# MainBoard_XMega.net
KiCad netlist of a schematic drawn in Altium Designer
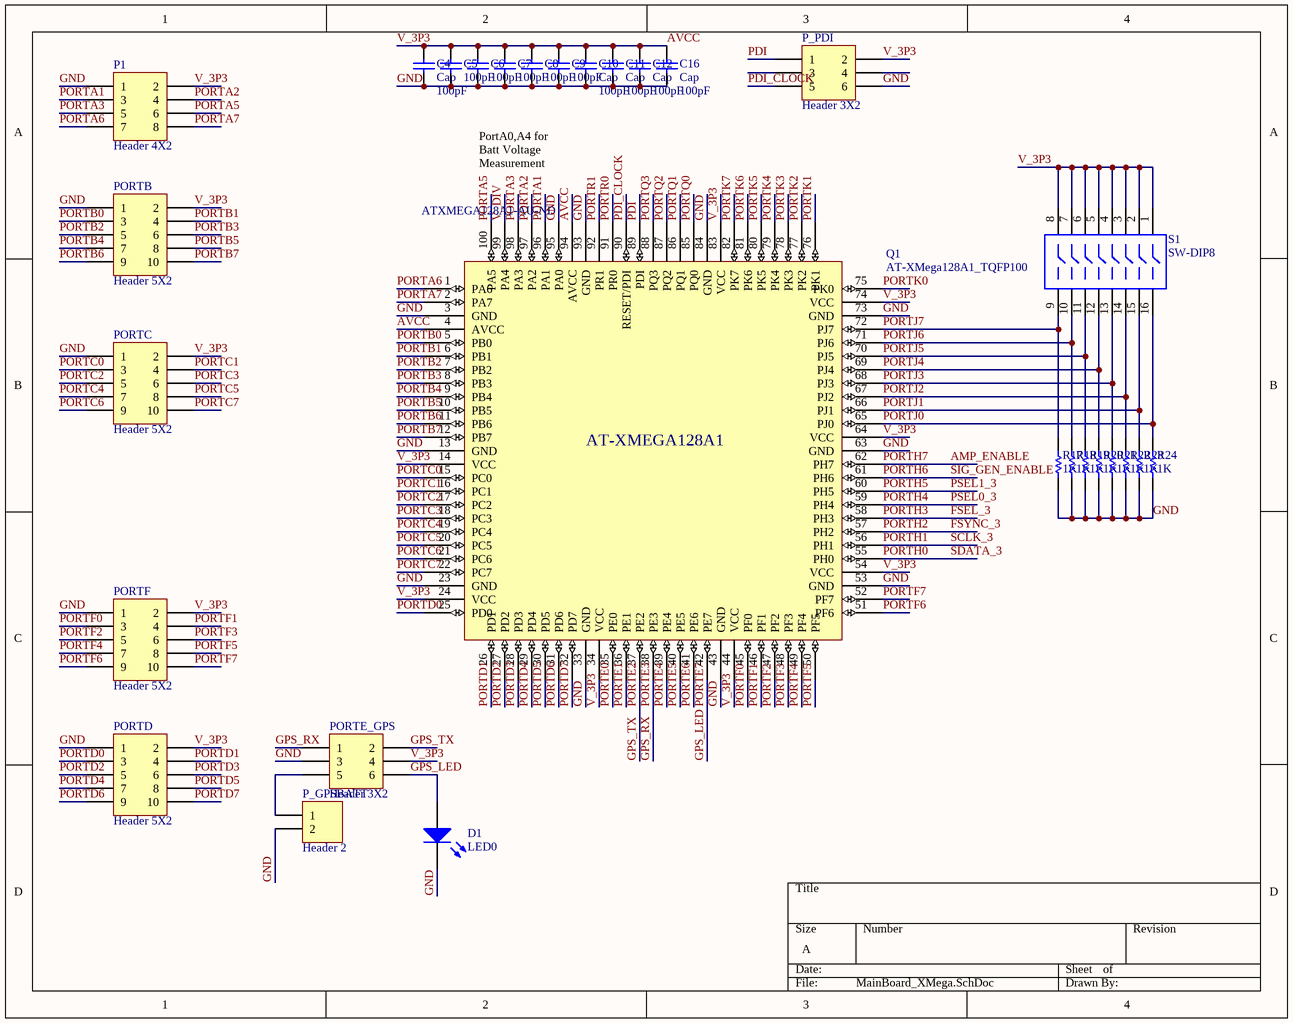
[diagram p0: MainBoard_XMega.SchDoc]

(export (version "E")
  (design (tool "Eeschema 10.0.6"))
  (components
    (comp (ref "C4")
      (value "Cap")
      (footprint "CAPR2.54-5.1x3.2")
      (description "Capacitor")
      (fields (field (name "ALTIUM_VALUE") "100pF") (field (name "PUBLISHER") "Altium Limited"))
      (libsource (lib "Miscellaneous Devices") (part "Cap"))
    )
    (comp (ref "C5")
      (value "100pF")
      (footprint "CAPR2.54-5.1x3.2")
      (description "Capacitor")
      (fields (field (name "Comment") "Cap") (field (name "PUBLISHER") "Altium Limited"))
      (libsource (lib "Miscellaneous Devices") (part "Cap"))
    )
    (comp (ref "C6")
      (value "100pF")
      (footprint "CAPR2.54-5.1x3.2")
      (description "Capacitor")
      (fields (field (name "Comment") "Cap") (field (name "PUBLISHER") "Altium Limited"))
      (libsource (lib "Miscellaneous Devices") (part "Cap"))
    )
    (comp (ref "C7")
      (value "100pF")
      (footprint "CAPR2.54-5.1x3.2")
      (description "Capacitor")
      (fields (field (name "Comment") "Cap") (field (name "PUBLISHER") "Altium Limited"))
      (libsource (lib "Miscellaneous Devices") (part "Cap"))
    )
    (comp (ref "C8")
      (value "100pF")
      (footprint "CAPR2.54-5.1x3.2")
      (description "Capacitor")
      (fields (field (name "Comment") "Cap") (field (name "PUBLISHER") "Altium Limited"))
      (libsource (lib "Miscellaneous Devices") (part "Cap"))
    )
    (comp (ref "C9")
      (value "100pF")
      (footprint "CAPR2.54-5.1x3.2")
      (description "Capacitor")
      (fields (field (name "Comment") "Cap") (field (name "PUBLISHER") "Altium Limited"))
      (libsource (lib "Miscellaneous Devices") (part "Cap"))
    )
    (comp (ref "C10")
      (value "Cap")
      (footprint "CAPR2.54-5.1x3.2")
      (description "Capacitor")
      (fields (field (name "ALTIUM_VALUE") "100pF") (field (name "PUBLISHER") "Altium Limited"))
      (libsource (lib "Miscellaneous Devices") (part "Cap"))
    )
    (comp (ref "C11")
      (value "Cap")
      (footprint "CAPR2.54-5.1x3.2")
      (description "Capacitor")
      (fields (field (name "ALTIUM_VALUE") "100pF") (field (name "PUBLISHER") "Altium Limited"))
      (libsource (lib "Miscellaneous Devices") (part "Cap"))
    )
    (comp (ref "C12")
      (value "Cap")
      (footprint "CAPR2.54-5.1x3.2")
      (description "Capacitor")
      (fields (field (name "ALTIUM_VALUE") "100pF") (field (name "PUBLISHER") "Altium Limited"))
      (libsource (lib "Miscellaneous Devices") (part "Cap"))
    )
    (comp (ref "C16")
      (value "Cap")
      (footprint "CAPR2.54-5.1x3.2")
      (description "Capacitor")
      (fields (field (name "ALTIUM_VALUE") "100pF") (field (name "PUBLISHER") "Altium Limited"))
      (libsource (lib "Miscellaneous Devices") (part "Cap"))
    )
    (comp (ref "D1")
      (value "LED0")
      (footprint "LED-0")
      (description "Typical INFRARED GaAs LED")
      (fields (field (name "PUBLISHER") "Altium Limited"))
      (libsource (lib "Miscellaneous Devices") (part "LED0"))
    )
    (comp (ref "P1")
      (value "Header 4X2")
      (footprint "HDR2X4")
      (description "Header, 4-Pin, Dual row")
      (fields (field (name "PUBLISHER") "Altium Limited"))
      (libsource (lib "Miscellaneous Connectors") (part "Header 4X2"))
    )
    (comp (ref "PORTB")
      (value "Header 5X2")
      (footprint "HDR2X5")
      (description "Header, 5-Pin, Dual row")
      (fields (field (name "PUBLISHER") "Altium Limited"))
      (libsource (lib "Miscellaneous Connectors") (part "Header 5X2"))
    )
    (comp (ref "PORTC")
      (value "Header 5X2")
      (footprint "HDR2X5")
      (description "Header, 5-Pin, Dual row")
      (fields (field (name "PUBLISHER") "Altium Limited"))
      (libsource (lib "Miscellaneous Connectors") (part "Header 5X2"))
    )
    (comp (ref "PORTD")
      (value "Header 5X2")
      (footprint "HDR2X5")
      (description "Header, 5-Pin, Dual row")
      (fields (field (name "PUBLISHER") "Altium Limited"))
      (libsource (lib "Miscellaneous Connectors") (part "Header 5X2"))
    )
    (comp (ref "PORTE_GPS")
      (value "Header 3X2")
      (footprint "HDR2X3")
      (description "Header, 3-Pin, Dual row")
      (fields (field (name "PUBLISHER") "Altium Limited"))
      (libsource (lib "Miscellaneous Connectors") (part "Header 3X2"))
    )
    (comp (ref "PORTF")
      (value "Header 5X2")
      (footprint "HDR2X5")
      (description "Header, 5-Pin, Dual row")
      (fields (field (name "PUBLISHER") "Altium Limited"))
      (libsource (lib "Miscellaneous Connectors") (part "Header 5X2"))
    )
    (comp (ref "P_GPSBATT")
      (value "Header 2")
      (footprint "HDR1X2")
      (description "Header, 2-Pin")
      (fields (field (name "PUBLISHER") "Altium Limited"))
      (libsource (lib "Miscellaneous Connectors") (part "Header 2"))
    )
    (comp (ref "P_PDI")
      (value "Header 3X2")
      (footprint "HDR2X3")
      (description "Header, 3-Pin, Dual row")
      (fields (field (name "PUBLISHER") "Altium Limited"))
      (libsource (lib "Miscellaneous Connectors") (part "Header 3X2"))
    )
    (comp (ref "Q1")
      (value "AT-XMega128A1_TQFP100")
      (footprint "Altera Footprints:TQFP100_L")
      (fields (field (name "SUPPLIER PART NUMBER 1") "ATXMEGA128A1-AU-ND"))
      (libsource (lib "MainBoard_Lib") (part "AT-XMega128A1_TQFP100"))
    )
    (comp (ref "R17")
      (value "1K")
      (footprint "AXIAL-0.3")
      (description "Resistor")
      (fields (field (name "Comment") "Res1") (field (name "PUBLISHER") "Altium Limited"))
      (libsource (lib "Miscellaneous Devices") (part "Res1"))
    )
    (comp (ref "R18")
      (value "1K")
      (footprint "AXIAL-0.3")
      (description "Resistor")
      (fields (field (name "Comment") "Res1") (field (name "PUBLISHER") "Altium Limited"))
      (libsource (lib "Miscellaneous Devices") (part "Res1"))
    )
    (comp (ref "R19")
      (value "1K")
      (footprint "AXIAL-0.3")
      (description "Resistor")
      (fields (field (name "Comment") "Res1") (field (name "PUBLISHER") "Altium Limited"))
      (libsource (lib "Miscellaneous Devices") (part "Res1"))
    )
    (comp (ref "R20")
      (value "1K")
      (footprint "AXIAL-0.3")
      (description "Resistor")
      (fields (field (name "Comment") "Res1") (field (name "PUBLISHER") "Altium Limited"))
      (libsource (lib "Miscellaneous Devices") (part "Res1"))
    )
    (comp (ref "R21")
      (value "1K")
      (footprint "AXIAL-0.3")
      (description "Resistor")
      (fields (field (name "Comment") "Res1") (field (name "PUBLISHER") "Altium Limited"))
      (libsource (lib "Miscellaneous Devices") (part "Res1"))
    )
    (comp (ref "R22")
      (value "1K")
      (footprint "AXIAL-0.3")
      (description "Resistor")
      (fields (field (name "Comment") "Res1") (field (name "PUBLISHER") "Altium Limited"))
      (libsource (lib "Miscellaneous Devices") (part "Res1"))
    )
    (comp (ref "R23")
      (value "1K")
      (footprint "AXIAL-0.3")
      (description "Resistor")
      (fields (field (name "Comment") "Res1") (field (name "PUBLISHER") "Altium Limited"))
      (libsource (lib "Miscellaneous Devices") (part "Res1"))
    )
    (comp (ref "R24")
      (value "1K")
      (footprint "AXIAL-0.3")
      (description "Resistor")
      (fields (field (name "Comment") "Res1") (field (name "PUBLISHER") "Altium Limited"))
      (libsource (lib "Miscellaneous Devices") (part "Res1"))
    )
    (comp (ref "S1")
      (value "SW-DIP8")
      (footprint "DIP-16-KEY")
      (description "4009 Series DIP Switch, Raised actuator")
      (fields (field (name "PUBLISHER") "Altium Limited"))
      (libsource (lib "Miscellaneous Devices") (part "SW-DIP8"))
    )
  )
  (nets
    (net (code "1") (name "/AMP_ENABLE") (class "Default")
      (node (ref "Q1") (pin "62") (pinfunction "PH7_62") (pintype "bidirectional"))
    )
    (net (code "2") (name "/AVCC") (class "Default")
      (node (ref "C10") (pin "2") (pinfunction "2_2") (pintype "passive"))
      (node (ref "C11") (pin "2") (pinfunction "2_2") (pintype "passive"))
      (node (ref "C12") (pin "2") (pinfunction "2_2") (pintype "passive"))
      (node (ref "C16") (pin "2") (pinfunction "2_2") (pintype "passive"))
      (node (ref "C4") (pin "2") (pinfunction "2_2") (pintype "passive"))
      (node (ref "C5") (pin "2") (pinfunction "2_2") (pintype "passive"))
      (node (ref "C6") (pin "2") (pinfunction "2_2") (pintype "passive"))
      (node (ref "C7") (pin "2") (pinfunction "2_2") (pintype "passive"))
      (node (ref "C8") (pin "2") (pinfunction "2_2") (pintype "passive"))
      (node (ref "C9") (pin "2") (pinfunction "2_2") (pintype "passive"))
      (node (ref "P1") (pin "2") (pinfunction "2_2") (pintype "passive"))
      (node (ref "PORTB") (pin "2") (pinfunction "2_2") (pintype "passive"))
      (node (ref "PORTC") (pin "2") (pinfunction "2_2") (pintype "passive"))
      (node (ref "PORTD") (pin "2") (pinfunction "2_2") (pintype "passive"))
      (node (ref "PORTE_GPS") (pin "4") (pinfunction "4_4") (pintype "passive"))
      (node (ref "PORTF") (pin "2") (pinfunction "2_2") (pintype "passive"))
      (node (ref "P_PDI") (pin "2") (pinfunction "2_2") (pintype "passive"))
      (node (ref "Q1") (pin "14") (pinfunction "VCC_14") (pintype "power_in"))
      (node (ref "Q1") (pin "24") (pinfunction "VCC_24") (pintype "power_in"))
      (node (ref "Q1") (pin "34") (pinfunction "VCC_34") (pintype "power_in"))
      (node (ref "Q1") (pin "4") (pinfunction "AVCC_4") (pintype "power_in"))
      (node (ref "Q1") (pin "44") (pinfunction "VCC_44") (pintype "power_in"))
      (node (ref "Q1") (pin "54") (pinfunction "VCC_54") (pintype "power_in"))
      (node (ref "Q1") (pin "64") (pinfunction "VCC_64") (pintype "power_in"))
      (node (ref "Q1") (pin "74") (pinfunction "VCC_74") (pintype "power_in"))
      (node (ref "Q1") (pin "83") (pinfunction "VCC_83") (pintype "power_in"))
      (node (ref "Q1") (pin "94") (pinfunction "AVCC_94") (pintype "power_in"))
      (node (ref "S1") (pin "1") (pinfunction "1_1") (pintype "passive"))
      (node (ref "S1") (pin "2") (pinfunction "2_2") (pintype "passive"))
      (node (ref "S1") (pin "3") (pinfunction "3_3") (pintype "passive"))
      (node (ref "S1") (pin "4") (pinfunction "4_4") (pintype "passive"))
      (node (ref "S1") (pin "5") (pinfunction "5_5") (pintype "passive"))
      (node (ref "S1") (pin "6") (pinfunction "6_6") (pintype "passive"))
      (node (ref "S1") (pin "7") (pinfunction "7_7") (pintype "passive"))
      (node (ref "S1") (pin "8") (pinfunction "8_8") (pintype "passive"))
    )
    (net (code "3") (name "/FSEL_3") (class "Default")
      (node (ref "Q1") (pin "58") (pinfunction "PH3_58") (pintype "bidirectional"))
    )
    (net (code "4") (name "/FSYNC_3") (class "Default")
      (node (ref "Q1") (pin "57") (pinfunction "PH2_57") (pintype "bidirectional"))
    )
    (net (code "5") (name "/GND") (class "Default")
      (node (ref "C10") (pin "1") (pinfunction "1_1") (pintype "passive"))
      (node (ref "C11") (pin "1") (pinfunction "1_1") (pintype "passive"))
      (node (ref "C12") (pin "1") (pinfunction "1_1") (pintype "passive"))
      (node (ref "C16") (pin "1") (pinfunction "1_1") (pintype "passive"))
      (node (ref "C4") (pin "1") (pinfunction "1_1") (pintype "passive"))
      (node (ref "C5") (pin "1") (pinfunction "1_1") (pintype "passive"))
      (node (ref "C6") (pin "1") (pinfunction "1_1") (pintype "passive"))
      (node (ref "C7") (pin "1") (pinfunction "1_1") (pintype "passive"))
      (node (ref "C8") (pin "1") (pinfunction "1_1") (pintype "passive"))
      (node (ref "C9") (pin "1") (pinfunction "1_1") (pintype "passive"))
      (node (ref "D1") (pin "2") (pinfunction "K_2") (pintype "passive"))
      (node (ref "P1") (pin "1") (pinfunction "1_1") (pintype "passive"))
      (node (ref "PORTB") (pin "1") (pinfunction "1_1") (pintype "passive"))
      (node (ref "PORTC") (pin "1") (pinfunction "1_1") (pintype "passive"))
      (node (ref "PORTD") (pin "1") (pinfunction "1_1") (pintype "passive"))
      (node (ref "PORTE_GPS") (pin "3") (pinfunction "3_3") (pintype "passive"))
      (node (ref "PORTF") (pin "1") (pinfunction "1_1") (pintype "passive"))
      (node (ref "P_GPSBATT") (pin "2") (pinfunction "2_2") (pintype "passive"))
      (node (ref "P_PDI") (pin "6") (pinfunction "6_6") (pintype "passive"))
      (node (ref "Q1") (pin "13") (pinfunction "GND_13") (pintype "power_in"))
      (node (ref "Q1") (pin "23") (pinfunction "GND_23") (pintype "power_in"))
      (node (ref "Q1") (pin "3") (pinfunction "GND_3") (pintype "power_in"))
      (node (ref "Q1") (pin "33") (pinfunction "GND_33") (pintype "power_in"))
      (node (ref "Q1") (pin "43") (pinfunction "GND_43") (pintype "power_in"))
      (node (ref "Q1") (pin "53") (pinfunction "GND_53") (pintype "power_in"))
      (node (ref "Q1") (pin "63") (pinfunction "GND_63") (pintype "power_in"))
      (node (ref "Q1") (pin "73") (pinfunction "GND_73") (pintype "power_in"))
      (node (ref "Q1") (pin "84") (pinfunction "GND_84") (pintype "power_in"))
      (node (ref "Q1") (pin "93") (pinfunction "GND_93") (pintype "power_in"))
      (node (ref "Q1") (pin "95") (pinfunction "PA0_95") (pintype "bidirectional"))
      (node (ref "R17") (pin "1") (pinfunction "1_1") (pintype "passive"))
      (node (ref "R18") (pin "1") (pinfunction "1_1") (pintype "passive"))
      (node (ref "R19") (pin "1") (pinfunction "1_1") (pintype "passive"))
      (node (ref "R20") (pin "1") (pinfunction "1_1") (pintype "passive"))
      (node (ref "R21") (pin "1") (pinfunction "1_1") (pintype "passive"))
      (node (ref "R22") (pin "1") (pinfunction "1_1") (pintype "passive"))
      (node (ref "R23") (pin "1") (pinfunction "1_1") (pintype "passive"))
      (node (ref "R24") (pin "1") (pinfunction "1_1") (pintype "passive"))
    )
    (net (code "6") (name "/GPS_LED") (class "Default")
      (node (ref "D1") (pin "1") (pinfunction "A_1") (pintype "passive"))
      (node (ref "PORTE_GPS") (pin "6") (pinfunction "6_6") (pintype "passive"))
      (node (ref "Q1") (pin "42") (pinfunction "PE7_42") (pintype "bidirectional"))
    )
    (net (code "7") (name "/GPS_RX") (class "Default")
      (node (ref "PORTE_GPS") (pin "1") (pinfunction "1_1") (pintype "passive"))
      (node (ref "Q1") (pin "38") (pinfunction "PE3_38") (pintype "bidirectional"))
    )
    (net (code "8") (name "/GPS_TX") (class "Default")
      (node (ref "PORTE_GPS") (pin "2") (pinfunction "2_2") (pintype "passive"))
      (node (ref "Q1") (pin "37") (pinfunction "PE2_37") (pintype "bidirectional"))
    )
    (net (code "9") (name "/PDI") (class "Default")
      (node (ref "P_PDI") (pin "1") (pinfunction "1_1") (pintype "passive"))
      (node (ref "Q1") (pin "89") (pinfunction "PDI_89") (pintype "bidirectional"))
    )
    (net (code "10") (name "/PDI_CLOCK") (class "Default")
      (node (ref "P_PDI") (pin "5") (pinfunction "5_5") (pintype "passive"))
      (node (ref "Q1") (pin "90") (pinfunction "RESET/PDI_90") (pintype "bidirectional"))
    )
    (net (code "11") (name "/PORTA1") (class "Default")
      (node (ref "P1") (pin "3") (pinfunction "3_3") (pintype "passive"))
      (node (ref "Q1") (pin "96") (pinfunction "PA1_96") (pintype "bidirectional"))
    )
    (net (code "12") (name "/PORTA2") (class "Default")
      (node (ref "P1") (pin "4") (pinfunction "4_4") (pintype "passive"))
      (node (ref "Q1") (pin "97") (pinfunction "PA2_97") (pintype "bidirectional"))
    )
    (net (code "13") (name "/PORTA3") (class "Default")
      (node (ref "P1") (pin "5") (pinfunction "5_5") (pintype "passive"))
      (node (ref "Q1") (pin "98") (pinfunction "PA3_98") (pintype "bidirectional"))
    )
    (net (code "14") (name "/PORTA5") (class "Default")
      (node (ref "P1") (pin "6") (pinfunction "6_6") (pintype "passive"))
      (node (ref "Q1") (pin "100") (pinfunction "PA5_100") (pintype "bidirectional"))
    )
    (net (code "15") (name "/PORTA6") (class "Default")
      (node (ref "P1") (pin "7") (pinfunction "7_7") (pintype "passive"))
      (node (ref "Q1") (pin "1") (pinfunction "PA6_1") (pintype "bidirectional"))
    )
    (net (code "16") (name "/PORTA7") (class "Default")
      (node (ref "P1") (pin "8") (pinfunction "8_8") (pintype "passive"))
      (node (ref "Q1") (pin "2") (pinfunction "PA7_2") (pintype "bidirectional"))
    )
    (net (code "17") (name "/PORTB0") (class "Default")
      (node (ref "PORTB") (pin "3") (pinfunction "3_3") (pintype "passive"))
      (node (ref "Q1") (pin "5") (pinfunction "PB0_5") (pintype "bidirectional"))
    )
    (net (code "18") (name "/PORTB1") (class "Default")
      (node (ref "PORTB") (pin "4") (pinfunction "4_4") (pintype "passive"))
      (node (ref "Q1") (pin "6") (pinfunction "PB1_6") (pintype "bidirectional"))
    )
    (net (code "19") (name "/PORTB2") (class "Default")
      (node (ref "PORTB") (pin "5") (pinfunction "5_5") (pintype "passive"))
      (node (ref "Q1") (pin "7") (pinfunction "PB2_7") (pintype "bidirectional"))
    )
    (net (code "20") (name "/PORTB3") (class "Default")
      (node (ref "PORTB") (pin "6") (pinfunction "6_6") (pintype "passive"))
      (node (ref "Q1") (pin "8") (pinfunction "PB3_8") (pintype "bidirectional"))
    )
    (net (code "21") (name "/PORTB4") (class "Default")
      (node (ref "PORTB") (pin "7") (pinfunction "7_7") (pintype "passive"))
      (node (ref "Q1") (pin "9") (pinfunction "PB4_9") (pintype "bidirectional"))
    )
    (net (code "22") (name "/PORTB5") (class "Default")
      (node (ref "PORTB") (pin "8") (pinfunction "8_8") (pintype "passive"))
      (node (ref "Q1") (pin "10") (pinfunction "PB5_10") (pintype "bidirectional"))
    )
    (net (code "23") (name "/PORTB6") (class "Default")
      (node (ref "PORTB") (pin "9") (pinfunction "9_9") (pintype "passive"))
      (node (ref "Q1") (pin "11") (pinfunction "PB6_11") (pintype "bidirectional"))
    )
    (net (code "24") (name "/PORTB7") (class "Default")
      (node (ref "PORTB") (pin "10") (pinfunction "10_10") (pintype "passive"))
      (node (ref "Q1") (pin "12") (pinfunction "PB7_12") (pintype "bidirectional"))
    )
    (net (code "25") (name "/PORTC0") (class "Default")
      (node (ref "PORTC") (pin "3") (pinfunction "3_3") (pintype "passive"))
      (node (ref "Q1") (pin "15") (pinfunction "PC0_15") (pintype "bidirectional"))
    )
    (net (code "26") (name "/PORTC1") (class "Default")
      (node (ref "PORTC") (pin "4") (pinfunction "4_4") (pintype "passive"))
      (node (ref "Q1") (pin "16") (pinfunction "PC1_16") (pintype "bidirectional"))
    )
    (net (code "27") (name "/PORTC2") (class "Default")
      (node (ref "PORTC") (pin "5") (pinfunction "5_5") (pintype "passive"))
      (node (ref "Q1") (pin "17") (pinfunction "PC2_17") (pintype "bidirectional"))
    )
    (net (code "28") (name "/PORTC3") (class "Default")
      (node (ref "PORTC") (pin "6") (pinfunction "6_6") (pintype "passive"))
      (node (ref "Q1") (pin "18") (pinfunction "PC3_18") (pintype "bidirectional"))
    )
    (net (code "29") (name "/PORTC4") (class "Default")
      (node (ref "PORTC") (pin "7") (pinfunction "7_7") (pintype "passive"))
      (node (ref "Q1") (pin "19") (pinfunction "PC4_19") (pintype "bidirectional"))
    )
    (net (code "30") (name "/PORTC5") (class "Default")
      (node (ref "PORTC") (pin "8") (pinfunction "8_8") (pintype "passive"))
      (node (ref "Q1") (pin "20") (pinfunction "PC5_20") (pintype "bidirectional"))
    )
    (net (code "31") (name "/PORTC6") (class "Default")
      (node (ref "PORTC") (pin "9") (pinfunction "9_9") (pintype "passive"))
      (node (ref "Q1") (pin "21") (pinfunction "PC6_21") (pintype "bidirectional"))
    )
    (net (code "32") (name "/PORTC7") (class "Default")
      (node (ref "PORTC") (pin "10") (pinfunction "10_10") (pintype "passive"))
      (node (ref "Q1") (pin "22") (pinfunction "PC7_22") (pintype "bidirectional"))
    )
    (net (code "33") (name "/PORTD0") (class "Default")
      (node (ref "PORTD") (pin "3") (pinfunction "3_3") (pintype "passive"))
      (node (ref "Q1") (pin "25") (pinfunction "PD0_25") (pintype "bidirectional"))
    )
    (net (code "34") (name "/PORTD1") (class "Default")
      (node (ref "PORTD") (pin "4") (pinfunction "4_4") (pintype "passive"))
      (node (ref "Q1") (pin "26") (pinfunction "PD1_26") (pintype "bidirectional"))
    )
    (net (code "35") (name "/PORTD2") (class "Default")
      (node (ref "PORTD") (pin "5") (pinfunction "5_5") (pintype "passive"))
      (node (ref "Q1") (pin "27") (pinfunction "PD2_27") (pintype "bidirectional"))
    )
    (net (code "36") (name "/PORTD3") (class "Default")
      (node (ref "PORTD") (pin "6") (pinfunction "6_6") (pintype "passive"))
      (node (ref "Q1") (pin "28") (pinfunction "PD3_28") (pintype "bidirectional"))
    )
    (net (code "37") (name "/PORTD4") (class "Default")
      (node (ref "PORTD") (pin "7") (pinfunction "7_7") (pintype "passive"))
      (node (ref "Q1") (pin "29") (pinfunction "PD4_29") (pintype "bidirectional"))
    )
    (net (code "38") (name "/PORTD5") (class "Default")
      (node (ref "PORTD") (pin "8") (pinfunction "8_8") (pintype "passive"))
      (node (ref "Q1") (pin "30") (pinfunction "PD5_30") (pintype "bidirectional"))
    )
    (net (code "39") (name "/PORTD6") (class "Default")
      (node (ref "PORTD") (pin "9") (pinfunction "9_9") (pintype "passive"))
      (node (ref "Q1") (pin "31") (pinfunction "PD6_31") (pintype "bidirectional"))
    )
    (net (code "40") (name "/PORTD7") (class "Default")
      (node (ref "PORTD") (pin "10") (pinfunction "10_10") (pintype "passive"))
      (node (ref "Q1") (pin "32") (pinfunction "PD7_32") (pintype "bidirectional"))
    )
    (net (code "41") (name "/PORTE0") (class "Default")
      (node (ref "Q1") (pin "35") (pinfunction "PE0_35") (pintype "bidirectional"))
    )
    (net (code "42") (name "/PORTE1") (class "Default")
      (node (ref "Q1") (pin "36") (pinfunction "PE1_36") (pintype "bidirectional"))
    )
    (net (code "43") (name "/PORTE4") (class "Default")
      (node (ref "Q1") (pin "39") (pinfunction "PE4_39") (pintype "bidirectional"))
    )
    (net (code "44") (name "/PORTE5") (class "Default")
      (node (ref "Q1") (pin "40") (pinfunction "PE5_40") (pintype "bidirectional"))
    )
    (net (code "45") (name "/PORTE6") (class "Default")
      (node (ref "Q1") (pin "41") (pinfunction "PE6_41") (pintype "bidirectional"))
    )
    (net (code "46") (name "/PORTF0") (class "Default")
      (node (ref "PORTF") (pin "3") (pinfunction "3_3") (pintype "passive"))
      (node (ref "Q1") (pin "45") (pinfunction "PF0_45") (pintype "bidirectional"))
    )
    (net (code "47") (name "/PORTF1") (class "Default")
      (node (ref "PORTF") (pin "4") (pinfunction "4_4") (pintype "passive"))
      (node (ref "Q1") (pin "46") (pinfunction "PF1_46") (pintype "bidirectional"))
    )
    (net (code "48") (name "/PORTF2") (class "Default")
      (node (ref "PORTF") (pin "5") (pinfunction "5_5") (pintype "passive"))
      (node (ref "Q1") (pin "47") (pinfunction "PF2_47") (pintype "bidirectional"))
    )
    (net (code "49") (name "/PORTF3") (class "Default")
      (node (ref "PORTF") (pin "6") (pinfunction "6_6") (pintype "passive"))
      (node (ref "Q1") (pin "48") (pinfunction "PF3_48") (pintype "bidirectional"))
    )
    (net (code "50") (name "/PORTF4") (class "Default")
      (node (ref "PORTF") (pin "7") (pinfunction "7_7") (pintype "passive"))
      (node (ref "Q1") (pin "49") (pinfunction "PF4_49") (pintype "bidirectional"))
    )
    (net (code "51") (name "/PORTF5") (class "Default")
      (node (ref "PORTF") (pin "8") (pinfunction "8_8") (pintype "passive"))
      (node (ref "Q1") (pin "50") (pinfunction "PF5_50") (pintype "bidirectional"))
    )
    (net (code "52") (name "/PORTF6") (class "Default")
      (node (ref "PORTF") (pin "9") (pinfunction "9_9") (pintype "passive"))
      (node (ref "Q1") (pin "51") (pinfunction "PF6_51") (pintype "bidirectional"))
    )
    (net (code "53") (name "/PORTF7") (class "Default")
      (node (ref "PORTF") (pin "10") (pinfunction "10_10") (pintype "passive"))
      (node (ref "Q1") (pin "52") (pinfunction "PF7_52") (pintype "bidirectional"))
    )
    (net (code "54") (name "/PORTH0") (class "Default")
      (node (ref "Q1") (pin "55") (pinfunction "PH0_55") (pintype "bidirectional"))
    )
    (net (code "55") (name "/PORTH1") (class "Default")
      (node (ref "Q1") (pin "56") (pinfunction "PH1_56") (pintype "bidirectional"))
    )
    (net (code "56") (name "/PORTH4") (class "Default")
      (node (ref "Q1") (pin "59") (pinfunction "PH4_59") (pintype "bidirectional"))
    )
    (net (code "57") (name "/PORTH5") (class "Default")
      (node (ref "Q1") (pin "60") (pinfunction "PH5_60") (pintype "bidirectional"))
    )
    (net (code "58") (name "/PORTH6") (class "Default")
      (node (ref "Q1") (pin "61") (pinfunction "PH6_61") (pintype "bidirectional"))
    )
    (net (code "59") (name "/PORTJ0") (class "Default")
      (node (ref "Q1") (pin "65") (pinfunction "PJ0_65") (pintype "bidirectional"))
      (node (ref "R24") (pin "2") (pinfunction "2_2") (pintype "passive"))
      (node (ref "S1") (pin "16") (pinfunction "16_16") (pintype "passive"))
    )
    (net (code "60") (name "/PORTJ1") (class "Default")
      (node (ref "Q1") (pin "66") (pinfunction "PJ1_66") (pintype "bidirectional"))
      (node (ref "R23") (pin "2") (pinfunction "2_2") (pintype "passive"))
      (node (ref "S1") (pin "15") (pinfunction "15_15") (pintype "passive"))
    )
    (net (code "61") (name "/PORTJ2") (class "Default")
      (node (ref "Q1") (pin "67") (pinfunction "PJ2_67") (pintype "bidirectional"))
      (node (ref "R22") (pin "2") (pinfunction "2_2") (pintype "passive"))
      (node (ref "S1") (pin "14") (pinfunction "14_14") (pintype "passive"))
    )
    (net (code "62") (name "/PORTJ3") (class "Default")
      (node (ref "Q1") (pin "68") (pinfunction "PJ3_68") (pintype "bidirectional"))
      (node (ref "R21") (pin "2") (pinfunction "2_2") (pintype "passive"))
      (node (ref "S1") (pin "13") (pinfunction "13_13") (pintype "passive"))
    )
    (net (code "63") (name "/PORTJ4") (class "Default")
      (node (ref "Q1") (pin "69") (pinfunction "PJ4_69") (pintype "bidirectional"))
      (node (ref "R20") (pin "2") (pinfunction "2_2") (pintype "passive"))
      (node (ref "S1") (pin "12") (pinfunction "12_12") (pintype "passive"))
    )
    (net (code "64") (name "/PORTJ5") (class "Default")
      (node (ref "Q1") (pin "70") (pinfunction "PJ5_70") (pintype "bidirectional"))
      (node (ref "R19") (pin "2") (pinfunction "2_2") (pintype "passive"))
      (node (ref "S1") (pin "11") (pinfunction "11_11") (pintype "passive"))
    )
    (net (code "65") (name "/PORTJ6") (class "Default")
      (node (ref "Q1") (pin "71") (pinfunction "PJ6_71") (pintype "bidirectional"))
      (node (ref "R18") (pin "2") (pinfunction "2_2") (pintype "passive"))
      (node (ref "S1") (pin "10") (pinfunction "10_10") (pintype "passive"))
    )
    (net (code "66") (name "/PORTJ7") (class "Default")
      (node (ref "Q1") (pin "72") (pinfunction "PJ7_72") (pintype "bidirectional"))
      (node (ref "R17") (pin "2") (pinfunction "2_2") (pintype "passive"))
      (node (ref "S1") (pin "9") (pinfunction "9_9") (pintype "passive"))
    )
    (net (code "67") (name "/PORTK0") (class "Default")
      (node (ref "Q1") (pin "75") (pinfunction "PK0_75") (pintype "bidirectional"))
    )
    (net (code "68") (name "/PORTK1") (class "Default")
      (node (ref "Q1") (pin "76") (pinfunction "PK1_76") (pintype "bidirectional"))
    )
    (net (code "69") (name "/PORTK2") (class "Default")
      (node (ref "Q1") (pin "77") (pinfunction "PK2_77") (pintype "bidirectional"))
    )
    (net (code "70") (name "/PORTK3") (class "Default")
      (node (ref "Q1") (pin "78") (pinfunction "PK3_78") (pintype "bidirectional"))
    )
    (net (code "71") (name "/PORTK4") (class "Default")
      (node (ref "Q1") (pin "79") (pinfunction "PK4_79") (pintype "bidirectional"))
    )
    (net (code "72") (name "/PORTK5") (class "Default")
      (node (ref "Q1") (pin "80") (pinfunction "PK5_80") (pintype "bidirectional"))
    )
    (net (code "73") (name "/PORTK6") (class "Default")
      (node (ref "Q1") (pin "81") (pinfunction "PK6_81") (pintype "bidirectional"))
    )
    (net (code "74") (name "/PORTK7") (class "Default")
      (node (ref "Q1") (pin "82") (pinfunction "PK7_82") (pintype "bidirectional"))
    )
    (net (code "75") (name "/PORTQ0") (class "Default")
      (node (ref "Q1") (pin "85") (pinfunction "PQ0_85") (pintype "passive"))
    )
    (net (code "76") (name "/PORTQ1") (class "Default")
      (node (ref "Q1") (pin "86") (pinfunction "PQ1_86") (pintype "passive"))
    )
    (net (code "77") (name "/PORTQ2") (class "Default")
      (node (ref "Q1") (pin "87") (pinfunction "PQ2_87") (pintype "passive"))
    )
    (net (code "78") (name "/PORTQ3") (class "Default")
      (node (ref "Q1") (pin "88") (pinfunction "PQ3_88") (pintype "passive"))
    )
    (net (code "79") (name "/PORTR0") (class "Default")
      (node (ref "Q1") (pin "91") (pinfunction "PR0_91") (pintype "passive"))
    )
    (net (code "80") (name "/PORTR1") (class "Default")
      (node (ref "Q1") (pin "92") (pinfunction "PR1_92") (pintype "passive"))
    )
    (net (code "81") (name "/V_DIV") (class "Default")
      (node (ref "Q1") (pin "99") (pinfunction "PA4_99") (pintype "bidirectional"))
    )
    (net (code "82") (name "Net-(PORTE_GPS-Pad5)") (class "Default")
      (node (ref "PORTE_GPS") (pin "5") (pinfunction "5_5") (pintype "passive"))
      (node (ref "P_GPSBATT") (pin "1") (pinfunction "1_1") (pintype "passive"))
    )
    (net (code "83") (name "unconnected-(P_PDI-Pad3)") (class "Default")
      (node (ref "P_PDI") (pin "3") (pinfunction "3_3") (pintype "passive"))
    )
    (net (code "84") (name "unconnected-(P_PDI-Pad4)") (class "Default")
      (node (ref "P_PDI") (pin "4") (pinfunction "4_4") (pintype "passive"))
    )
  )
)
